# PlacaSensor_MPXV7002.net
KiCad netlist of a schematic drawn in Altium Designer
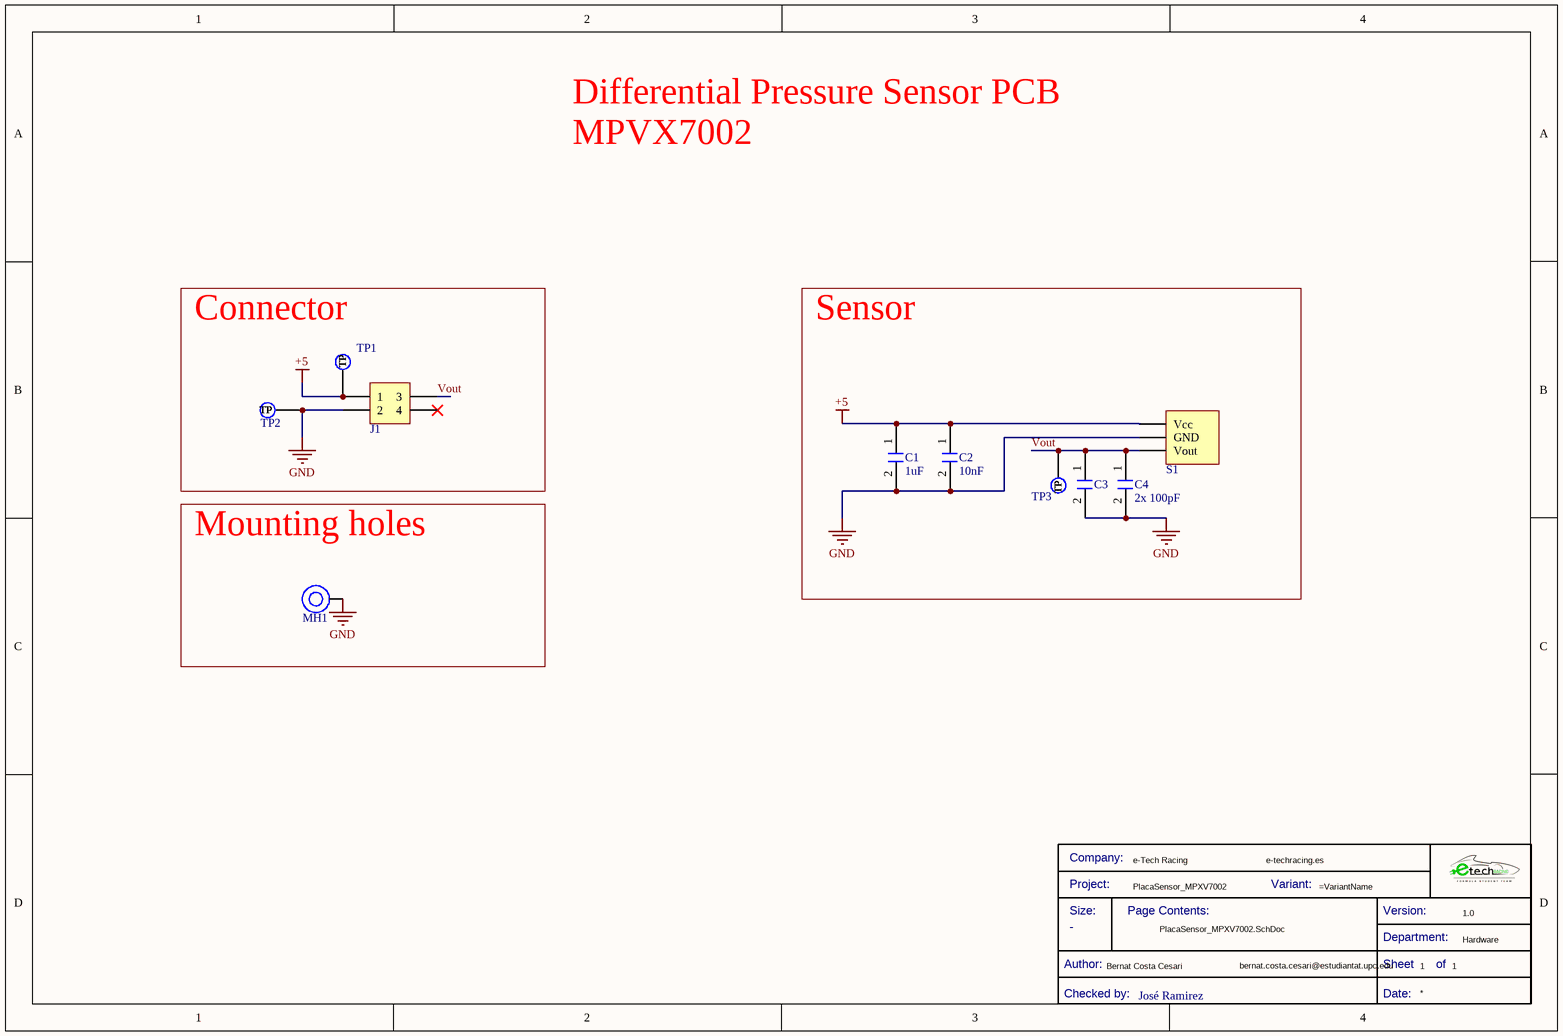
[diagram p0: PlacaSensor_MPXV7002.SchDoc]

(export (version "E")
  (design (tool "Eeschema 10.0.6"))
  (components
    (comp (ref "*")
      (value "Title Block_template")
      (description "Standard Title Block")
      (fields
        (field (name "SIZE") "-")
        (field (name ".CREATOR") "GP")
        (field (name ".PCBCHECK") "GP")
        (field (name ".SCHCHECK") "GP")
      )
      (libsource (lib "e-Tech_Racing") (part "Title Block_template"))
    )
    (comp (ref "C1")
      (value "885012207103")
      (footprint "C0805FNPC-R")
      (fields
        (field (name "TOLERANCE") "10%")
        (field (name "CAPACITANCE") "1uF")
        (field (name ".CREATOR") "GP")
      )
      (libsource (lib "Passives") (part "C1u-50V-0805FNPC-X7R"))
    )
    (comp (ref "C2")
      (value "885012207092")
      (footprint "C0805FNPC-R")
      (description "Cap, 0.01ΜF, 50V, 10%, X7R, 0805")
      (fields
        (field (name "TOLERANCE") "10%")
        (field (name "CAPACITANCE") "10nF")
        (field (name ".CREATOR") "DR")
      )
      (libsource (lib "Passives") (part "C10n-50V-0805FNPC-X7R"))
    )
    (comp (ref "C3")
      (value "885012007057")
      (footprint "C0805FNPC-W")
      (fields
        (field (name "MANUFACTURER") "Wurth Electronics")
        (field (name "TOLERANCE") "5%")
        (field (name ".CREATOR") "DR")
      )
      (libsource (lib "Passives") (part "C100p-50V-0805FNPC-C0G/NP0"))
    )
    (comp (ref "C4")
      (value "885012007057")
      (footprint "C0805FNPC-W")
      (fields
        (field (name "MANUFACTURER") "Wurth Electronics")
        (field (name "TOLERANCE") "5%")
        (field (name "CAPACITANCE") "2x 100pF")
        (field (name ".CREATOR") "DR")
      )
      (libsource (lib "Passives") (part "C100p-50V-0805FNPC-C0G/NP0"))
    )
    (comp (ref "J1")
      (value "J_NanoFit_2x2")
      (footprint "J_NanoFit_2x2_v")
      (description "Conn Nano-Fit Power HDR 4 POS 2.5mm Solder ST Through Hole 4 Terminal Single Port Tray")
      (libsource (lib "Electromechanical") (part "J_NanoFit_2x2"))
    )
    (comp (ref "MH1")
      (value "Mounting_Hole_M3")
      (footprint "Mounting_Hole_M3")
      (libsource (lib "Electromechanical") (part "Mounting_Hole_M3"))
    )
    (comp (ref "S1")
      (value "MPXV7002")
      (footprint "XDCR_MPXV7002DP")
      (libsource (lib "Sensors") (part "MPXV7002"))
    )
    (comp (ref "TP1")
      (value "TestPoint")
      (footprint "TestPoint")
      (description "Test Point 1x1 mm")
      (fields (field (name ".CREATOR") "GP") (field (name ".PCBCHECK") "GP") (field (name ".SCHCHECK") "GP"))
      (libsource (lib "e-Tech_Racing") (part "TestPoint"))
    )
    (comp (ref "TP2")
      (value "Test Point")
      (footprint "TESTPOINT_WIDE")
      (description "TestPoint 5x5mm")
      (libsource (lib "e-Tech_Racing") (part "TestPoint_Wide"))
    )
    (comp (ref "TP3")
      (value "TestPoint")
      (footprint "TestPoint")
      (description "Test Point 1x1 mm")
      (fields (field (name ".CREATOR") "GP") (field (name ".PCBCHECK") "GP") (field (name ".SCHCHECK") "GP"))
      (libsource (lib "e-Tech_Racing") (part "TestPoint"))
    )
  )
  (nets
    (net (code "1") (name "+5") (class "Default")
      (node (ref "C1") (pin "1") (pinfunction "1_1") (pintype "passive"))
      (node (ref "C2") (pin "1") (pinfunction "1_1") (pintype "passive"))
      (node (ref "J1") (pin "1") (pinfunction "1_1") (pintype "passive"))
      (node (ref "S1") (pin "2") (pinfunction "Vcc_2") (pintype "passive"))
      (node (ref "TP1") (pin "1") (pinfunction "TP_1") (pintype "passive"))
    )
    (net (code "2") (name "/Vout") (class "Default")
      (node (ref "C3") (pin "1") (pinfunction "1_1") (pintype "passive"))
      (node (ref "C4") (pin "1") (pinfunction "1_1") (pintype "passive"))
      (node (ref "J1") (pin "3") (pinfunction "3_3") (pintype "passive"))
      (node (ref "S1") (pin "4") (pinfunction "Vout_4") (pintype "passive"))
      (node (ref "TP3") (pin "1") (pinfunction "TP_1") (pintype "passive"))
    )
    (net (code "3") (name "GND") (class "Default")
      (node (ref "C1") (pin "2") (pinfunction "2_2") (pintype "passive"))
      (node (ref "C2") (pin "2") (pinfunction "2_2") (pintype "passive"))
      (node (ref "C3") (pin "2") (pinfunction "2_2") (pintype "passive"))
      (node (ref "C4") (pin "2") (pinfunction "2_2") (pintype "passive"))
      (node (ref "J1") (pin "2") (pinfunction "2_2") (pintype "passive"))
      (node (ref "MH1") (pin "1") (pinfunction "1_1") (pintype "passive"))
      (node (ref "S1") (pin "3") (pinfunction "GND_3") (pintype "passive"))
      (node (ref "TP2") (pin "1") (pinfunction "TP_1") (pintype "passive"))
    )
    (net (code "4") (name "unconnected-(J1-Pad4)") (class "Default")
      (node (ref "J1") (pin "4") (pinfunction "4_4") (pintype "passive+no_connect"))
    )
  )
)
